# Power_Distribution.net
KiCad netlist of a schematic drawn in EAGLE
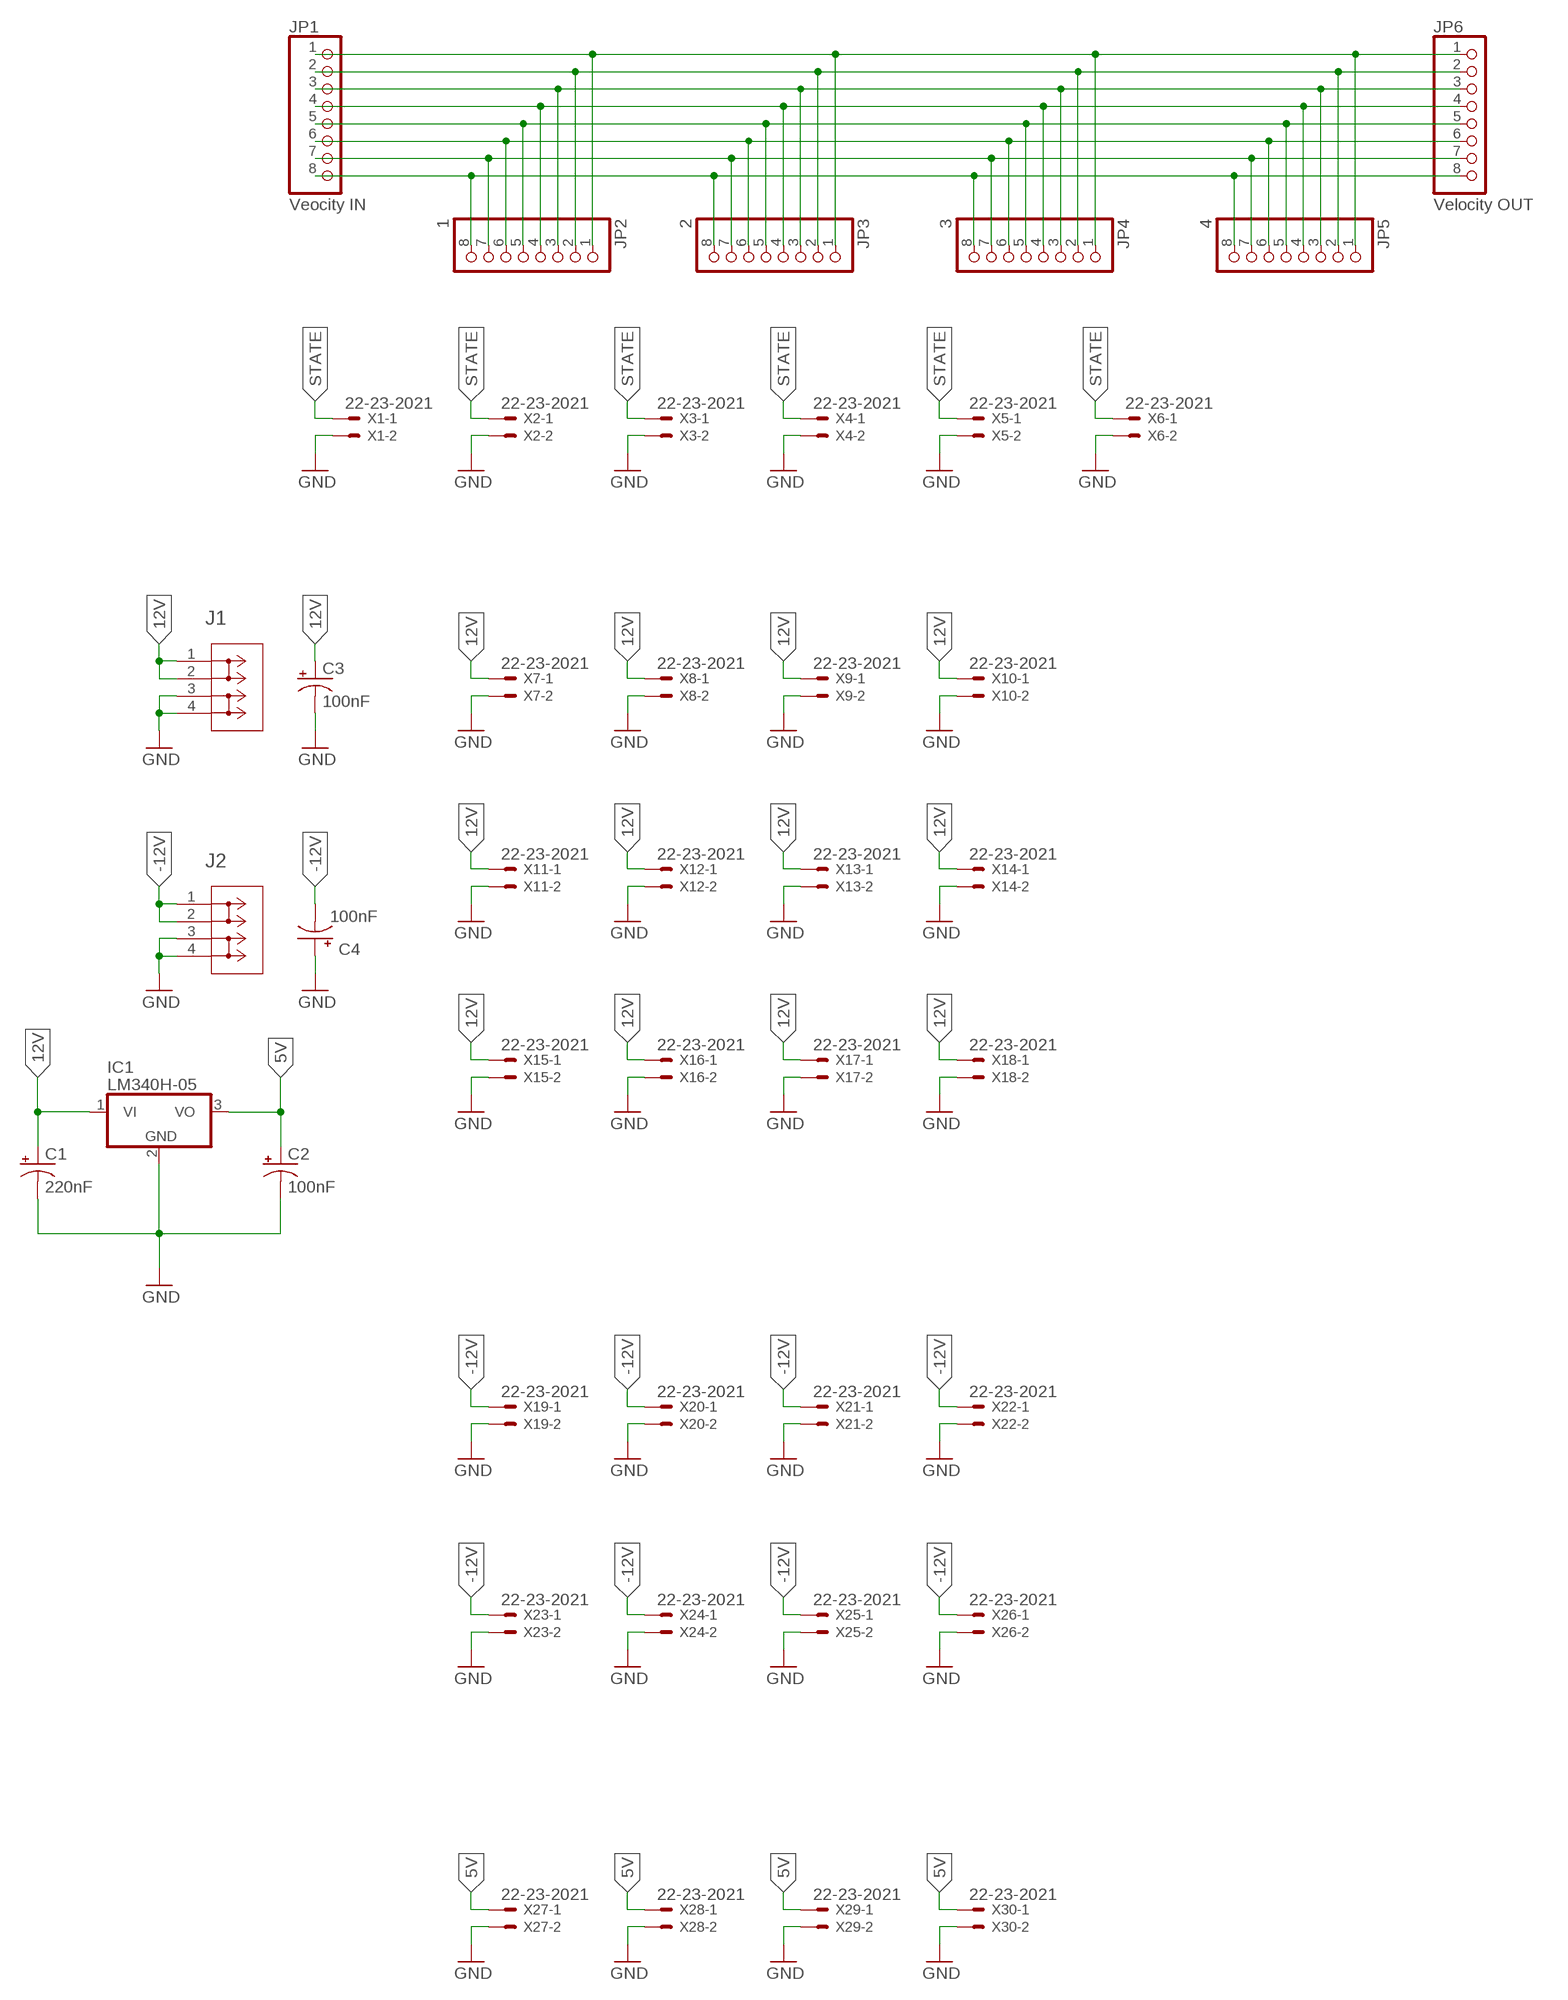
[diagram p0: schematic, sheet 1]

(export (version "E")
  (design (tool "Eeschema 10.0.6"))
  (components
    (comp (ref "C1")
      (value "220nF")
      (footprint "eagle-import:E2-5")
      (libsource (lib "eagle-import") (part "CPOL-USE2-5"))
    )
    (comp (ref "C2")
      (value "100nF")
      (footprint "eagle-import:E1,8-4")
      (libsource (lib "eagle-import") (part "CPOL-USE1.8-4"))
    )
    (comp (ref "C3")
      (value "100nF")
      (footprint "eagle-import:E1,8-4")
      (libsource (lib "eagle-import") (part "CPOL-USE1.8-4"))
    )
    (comp (ref "C4")
      (value "100nF")
      (footprint "eagle-import:E1,8-4")
      (libsource (lib "eagle-import") (part "CPOL-USE1.8-4"))
    )
    (comp (ref "IC1")
      (value "LM340H-05")
      (footprint "eagle-import:TO220H")
      (libsource (lib "eagle-import") (part "LM340?-H05"))
    )
    (comp (ref "J1")
      (value "691256610002")
      (footprint "eagle-import:CONN_691256610002_WRE")
      (fields (field (name "COPYRIGHT") "Copyright (C) 2024 Ultra Librarian. All rights reserved."))
      (libsource (lib "eagle-import") (part "691256610002"))
    )
    (comp (ref "J2")
      (value "691256610002")
      (footprint "eagle-import:CONN_691256610002_WRE")
      (fields (field (name "COPYRIGHT") "Copyright (C) 2024 Ultra Librarian. All rights reserved."))
      (libsource (lib "eagle-import") (part "691256610002"))
    )
    (comp (ref "JP1")
      (value "Veocity IN")
      (footprint "eagle-import:1X08-BIG")
      (libsource (lib "eagle-import") (part "PINHD-1X8BIG"))
    )
    (comp (ref "JP2")
      (value "1")
      (footprint "eagle-import:1X08-BIG")
      (libsource (lib "eagle-import") (part "PINHD-1X8BIG"))
    )
    (comp (ref "JP3")
      (value "2")
      (footprint "eagle-import:1X08-BIG")
      (libsource (lib "eagle-import") (part "PINHD-1X8BIG"))
    )
    (comp (ref "JP4")
      (value "3")
      (footprint "eagle-import:1X08-BIG")
      (libsource (lib "eagle-import") (part "PINHD-1X8BIG"))
    )
    (comp (ref "JP5")
      (value "4")
      (footprint "eagle-import:1X08-BIG")
      (libsource (lib "eagle-import") (part "PINHD-1X8BIG"))
    )
    (comp (ref "JP6")
      (value "Velocity OUT")
      (footprint "eagle-import:1X08-BIG")
      (libsource (lib "eagle-import") (part "PINHD-1X8BIG"))
    )
    (comp (ref "X1")
      (value "22-23-2021")
      (footprint "eagle-import:22-23-2021")
      (fields (field (name "MF") "MOLEX"))
      (libsource (lib "eagle-import") (part "22-23-2021"))
    )
    (comp (ref "X2")
      (value "22-23-2021")
      (footprint "eagle-import:22-23-2021")
      (fields (field (name "MF") "MOLEX"))
      (libsource (lib "eagle-import") (part "22-23-2021"))
    )
    (comp (ref "X3")
      (value "22-23-2021")
      (footprint "eagle-import:22-23-2021")
      (fields (field (name "MF") "MOLEX"))
      (libsource (lib "eagle-import") (part "22-23-2021"))
    )
    (comp (ref "X4")
      (value "22-23-2021")
      (footprint "eagle-import:22-23-2021")
      (fields (field (name "MF") "MOLEX"))
      (libsource (lib "eagle-import") (part "22-23-2021"))
    )
    (comp (ref "X5")
      (value "22-23-2021")
      (footprint "eagle-import:22-23-2021")
      (fields (field (name "MF") "MOLEX"))
      (libsource (lib "eagle-import") (part "22-23-2021"))
    )
    (comp (ref "X6")
      (value "22-23-2021")
      (footprint "eagle-import:22-23-2021")
      (fields (field (name "MF") "MOLEX"))
      (libsource (lib "eagle-import") (part "22-23-2021"))
    )
    (comp (ref "X7")
      (value "22-23-2021")
      (footprint "eagle-import:22-23-2021")
      (fields (field (name "MF") "MOLEX"))
      (libsource (lib "eagle-import") (part "22-23-2021"))
    )
    (comp (ref "X8")
      (value "22-23-2021")
      (footprint "eagle-import:22-23-2021")
      (fields (field (name "MF") "MOLEX"))
      (libsource (lib "eagle-import") (part "22-23-2021"))
    )
    (comp (ref "X9")
      (value "22-23-2021")
      (footprint "eagle-import:22-23-2021")
      (fields (field (name "MF") "MOLEX"))
      (libsource (lib "eagle-import") (part "22-23-2021"))
    )
    (comp (ref "X10")
      (value "22-23-2021")
      (footprint "eagle-import:22-23-2021")
      (fields (field (name "MF") "MOLEX"))
      (libsource (lib "eagle-import") (part "22-23-2021"))
    )
    (comp (ref "X11")
      (value "22-23-2021")
      (footprint "eagle-import:22-23-2021")
      (fields (field (name "MF") "MOLEX"))
      (libsource (lib "eagle-import") (part "22-23-2021"))
    )
    (comp (ref "X12")
      (value "22-23-2021")
      (footprint "eagle-import:22-23-2021")
      (fields (field (name "MF") "MOLEX"))
      (libsource (lib "eagle-import") (part "22-23-2021"))
    )
    (comp (ref "X13")
      (value "22-23-2021")
      (footprint "eagle-import:22-23-2021")
      (fields (field (name "MF") "MOLEX"))
      (libsource (lib "eagle-import") (part "22-23-2021"))
    )
    (comp (ref "X14")
      (value "22-23-2021")
      (footprint "eagle-import:22-23-2021")
      (fields (field (name "MF") "MOLEX"))
      (libsource (lib "eagle-import") (part "22-23-2021"))
    )
    (comp (ref "X15")
      (value "22-23-2021")
      (footprint "eagle-import:22-23-2021")
      (fields (field (name "MF") "MOLEX"))
      (libsource (lib "eagle-import") (part "22-23-2021"))
    )
    (comp (ref "X16")
      (value "22-23-2021")
      (footprint "eagle-import:22-23-2021")
      (fields (field (name "MF") "MOLEX"))
      (libsource (lib "eagle-import") (part "22-23-2021"))
    )
    (comp (ref "X17")
      (value "22-23-2021")
      (footprint "eagle-import:22-23-2021")
      (fields (field (name "MF") "MOLEX"))
      (libsource (lib "eagle-import") (part "22-23-2021"))
    )
    (comp (ref "X18")
      (value "22-23-2021")
      (footprint "eagle-import:22-23-2021")
      (fields (field (name "MF") "MOLEX"))
      (libsource (lib "eagle-import") (part "22-23-2021"))
    )
    (comp (ref "X19")
      (value "22-23-2021")
      (footprint "eagle-import:22-23-2021")
      (fields (field (name "MF") "MOLEX"))
      (libsource (lib "eagle-import") (part "22-23-2021"))
    )
    (comp (ref "X20")
      (value "22-23-2021")
      (footprint "eagle-import:22-23-2021")
      (fields (field (name "MF") "MOLEX"))
      (libsource (lib "eagle-import") (part "22-23-2021"))
    )
    (comp (ref "X21")
      (value "22-23-2021")
      (footprint "eagle-import:22-23-2021")
      (fields (field (name "MF") "MOLEX"))
      (libsource (lib "eagle-import") (part "22-23-2021"))
    )
    (comp (ref "X22")
      (value "22-23-2021")
      (footprint "eagle-import:22-23-2021")
      (fields (field (name "MF") "MOLEX"))
      (libsource (lib "eagle-import") (part "22-23-2021"))
    )
    (comp (ref "X23")
      (value "22-23-2021")
      (footprint "eagle-import:22-23-2021")
      (fields (field (name "MF") "MOLEX"))
      (libsource (lib "eagle-import") (part "22-23-2021"))
    )
    (comp (ref "X24")
      (value "22-23-2021")
      (footprint "eagle-import:22-23-2021")
      (fields (field (name "MF") "MOLEX"))
      (libsource (lib "eagle-import") (part "22-23-2021"))
    )
    (comp (ref "X25")
      (value "22-23-2021")
      (footprint "eagle-import:22-23-2021")
      (fields (field (name "MF") "MOLEX"))
      (libsource (lib "eagle-import") (part "22-23-2021"))
    )
    (comp (ref "X26")
      (value "22-23-2021")
      (footprint "eagle-import:22-23-2021")
      (fields (field (name "MF") "MOLEX"))
      (libsource (lib "eagle-import") (part "22-23-2021"))
    )
    (comp (ref "X27")
      (value "22-23-2021")
      (footprint "eagle-import:22-23-2021")
      (fields (field (name "MF") "MOLEX"))
      (libsource (lib "eagle-import") (part "22-23-2021"))
    )
    (comp (ref "X28")
      (value "22-23-2021")
      (footprint "eagle-import:22-23-2021")
      (fields (field (name "MF") "MOLEX"))
      (libsource (lib "eagle-import") (part "22-23-2021"))
    )
    (comp (ref "X29")
      (value "22-23-2021")
      (footprint "eagle-import:22-23-2021")
      (fields (field (name "MF") "MOLEX"))
      (libsource (lib "eagle-import") (part "22-23-2021"))
    )
    (comp (ref "X30")
      (value "22-23-2021")
      (footprint "eagle-import:22-23-2021")
      (fields (field (name "MF") "MOLEX"))
      (libsource (lib "eagle-import") (part "22-23-2021"))
    )
  )
  (nets
    (net (code "1") (name "-12V") (class "Default")
      (node (ref "C4") (pin "-") (pinfunction "-_-") (pintype "passive"))
      (node (ref "J2") (pin "1") (pinfunction "1_1") (pintype "passive"))
      (node (ref "J2") (pin "2") (pinfunction "2_2") (pintype "passive"))
      (node (ref "X19") (pin "1") (pinfunction "S_1") (pintype "passive"))
      (node (ref "X20") (pin "1") (pinfunction "S_1") (pintype "passive"))
      (node (ref "X21") (pin "1") (pinfunction "S_1") (pintype "passive"))
      (node (ref "X22") (pin "1") (pinfunction "S_1") (pintype "passive"))
      (node (ref "X23") (pin "1") (pinfunction "S_1") (pintype "passive"))
      (node (ref "X24") (pin "1") (pinfunction "S_1") (pintype "passive"))
      (node (ref "X25") (pin "1") (pinfunction "S_1") (pintype "passive"))
      (node (ref "X26") (pin "1") (pinfunction "S_1") (pintype "passive"))
    )
    (net (code "2") (name "5V") (class "Default")
      (node (ref "C2") (pin "+") (pinfunction "+_+") (pintype "passive"))
      (node (ref "IC1") (pin "3") (pinfunction "VO_3") (pintype "passive"))
      (node (ref "X27") (pin "1") (pinfunction "S_1") (pintype "passive"))
      (node (ref "X28") (pin "1") (pinfunction "S_1") (pintype "passive"))
      (node (ref "X29") (pin "1") (pinfunction "S_1") (pintype "passive"))
      (node (ref "X30") (pin "1") (pinfunction "S_1") (pintype "passive"))
    )
    (net (code "3") (name "12V") (class "Default")
      (node (ref "C1") (pin "+") (pinfunction "+_+") (pintype "passive"))
      (node (ref "C3") (pin "+") (pinfunction "+_+") (pintype "passive"))
      (node (ref "IC1") (pin "1") (pinfunction "VI_1") (pintype "input"))
      (node (ref "J1") (pin "1") (pinfunction "1_1") (pintype "passive"))
      (node (ref "J1") (pin "2") (pinfunction "2_2") (pintype "passive"))
      (node (ref "X10") (pin "1") (pinfunction "S_1") (pintype "passive"))
      (node (ref "X11") (pin "1") (pinfunction "S_1") (pintype "passive"))
      (node (ref "X12") (pin "1") (pinfunction "S_1") (pintype "passive"))
      (node (ref "X13") (pin "1") (pinfunction "S_1") (pintype "passive"))
      (node (ref "X14") (pin "1") (pinfunction "S_1") (pintype "passive"))
      (node (ref "X15") (pin "1") (pinfunction "S_1") (pintype "passive"))
      (node (ref "X16") (pin "1") (pinfunction "S_1") (pintype "passive"))
      (node (ref "X17") (pin "1") (pinfunction "S_1") (pintype "passive"))
      (node (ref "X18") (pin "1") (pinfunction "S_1") (pintype "passive"))
      (node (ref "X7") (pin "1") (pinfunction "S_1") (pintype "passive"))
      (node (ref "X8") (pin "1") (pinfunction "S_1") (pintype "passive"))
      (node (ref "X9") (pin "1") (pinfunction "S_1") (pintype "passive"))
    )
    (net (code "4") (name "GND") (class "Default")
      (node (ref "C1") (pin "-") (pinfunction "-_-") (pintype "passive"))
      (node (ref "C2") (pin "-") (pinfunction "-_-") (pintype "passive"))
      (node (ref "C3") (pin "-") (pinfunction "-_-") (pintype "passive"))
      (node (ref "C4") (pin "+") (pinfunction "+_+") (pintype "passive"))
      (node (ref "IC1") (pin "2") (pinfunction "GND_2") (pintype "passive"))
      (node (ref "J1") (pin "3") (pinfunction "3_3") (pintype "passive"))
      (node (ref "J1") (pin "4") (pinfunction "4_4") (pintype "passive"))
      (node (ref "J2") (pin "3") (pinfunction "3_3") (pintype "passive"))
      (node (ref "J2") (pin "4") (pinfunction "4_4") (pintype "passive"))
      (node (ref "X1") (pin "2") (pinfunction "S_2") (pintype "passive"))
      (node (ref "X10") (pin "2") (pinfunction "S_2") (pintype "passive"))
      (node (ref "X11") (pin "2") (pinfunction "S_2") (pintype "passive"))
      (node (ref "X12") (pin "2") (pinfunction "S_2") (pintype "passive"))
      (node (ref "X13") (pin "2") (pinfunction "S_2") (pintype "passive"))
      (node (ref "X14") (pin "2") (pinfunction "S_2") (pintype "passive"))
      (node (ref "X15") (pin "2") (pinfunction "S_2") (pintype "passive"))
      (node (ref "X16") (pin "2") (pinfunction "S_2") (pintype "passive"))
      (node (ref "X17") (pin "2") (pinfunction "S_2") (pintype "passive"))
      (node (ref "X18") (pin "2") (pinfunction "S_2") (pintype "passive"))
      (node (ref "X19") (pin "2") (pinfunction "S_2") (pintype "passive"))
      (node (ref "X2") (pin "2") (pinfunction "S_2") (pintype "passive"))
      (node (ref "X20") (pin "2") (pinfunction "S_2") (pintype "passive"))
      (node (ref "X21") (pin "2") (pinfunction "S_2") (pintype "passive"))
      (node (ref "X22") (pin "2") (pinfunction "S_2") (pintype "passive"))
      (node (ref "X23") (pin "2") (pinfunction "S_2") (pintype "passive"))
      (node (ref "X24") (pin "2") (pinfunction "S_2") (pintype "passive"))
      (node (ref "X25") (pin "2") (pinfunction "S_2") (pintype "passive"))
      (node (ref "X26") (pin "2") (pinfunction "S_2") (pintype "passive"))
      (node (ref "X27") (pin "2") (pinfunction "S_2") (pintype "passive"))
      (node (ref "X28") (pin "2") (pinfunction "S_2") (pintype "passive"))
      (node (ref "X29") (pin "2") (pinfunction "S_2") (pintype "passive"))
      (node (ref "X3") (pin "2") (pinfunction "S_2") (pintype "passive"))
      (node (ref "X30") (pin "2") (pinfunction "S_2") (pintype "passive"))
      (node (ref "X4") (pin "2") (pinfunction "S_2") (pintype "passive"))
      (node (ref "X5") (pin "2") (pinfunction "S_2") (pintype "passive"))
      (node (ref "X6") (pin "2") (pinfunction "S_2") (pintype "passive"))
      (node (ref "X7") (pin "2") (pinfunction "S_2") (pintype "passive"))
      (node (ref "X8") (pin "2") (pinfunction "S_2") (pintype "passive"))
      (node (ref "X9") (pin "2") (pinfunction "S_2") (pintype "passive"))
    )
    (net (code "5") (name "Net-(JP1-Pad1)") (class "Default")
      (node (ref "JP1") (pin "1") (pinfunction "1_1") (pintype "passive"))
      (node (ref "JP2") (pin "1") (pinfunction "1_1") (pintype "passive"))
      (node (ref "JP3") (pin "1") (pinfunction "1_1") (pintype "passive"))
      (node (ref "JP4") (pin "1") (pinfunction "1_1") (pintype "passive"))
      (node (ref "JP5") (pin "1") (pinfunction "1_1") (pintype "passive"))
      (node (ref "JP6") (pin "1") (pinfunction "1_1") (pintype "passive"))
    )
    (net (code "6") (name "Net-(JP1-Pad2)") (class "Default")
      (node (ref "JP1") (pin "2") (pinfunction "2_2") (pintype "passive"))
      (node (ref "JP2") (pin "2") (pinfunction "2_2") (pintype "passive"))
      (node (ref "JP3") (pin "2") (pinfunction "2_2") (pintype "passive"))
      (node (ref "JP4") (pin "2") (pinfunction "2_2") (pintype "passive"))
      (node (ref "JP5") (pin "2") (pinfunction "2_2") (pintype "passive"))
      (node (ref "JP6") (pin "2") (pinfunction "2_2") (pintype "passive"))
    )
    (net (code "7") (name "Net-(JP1-Pad3)") (class "Default")
      (node (ref "JP1") (pin "3") (pinfunction "3_3") (pintype "passive"))
      (node (ref "JP2") (pin "3") (pinfunction "3_3") (pintype "passive"))
      (node (ref "JP3") (pin "3") (pinfunction "3_3") (pintype "passive"))
      (node (ref "JP4") (pin "3") (pinfunction "3_3") (pintype "passive"))
      (node (ref "JP5") (pin "3") (pinfunction "3_3") (pintype "passive"))
      (node (ref "JP6") (pin "3") (pinfunction "3_3") (pintype "passive"))
    )
    (net (code "8") (name "Net-(JP1-Pad4)") (class "Default")
      (node (ref "JP1") (pin "4") (pinfunction "4_4") (pintype "passive"))
      (node (ref "JP2") (pin "4") (pinfunction "4_4") (pintype "passive"))
      (node (ref "JP3") (pin "4") (pinfunction "4_4") (pintype "passive"))
      (node (ref "JP4") (pin "4") (pinfunction "4_4") (pintype "passive"))
      (node (ref "JP5") (pin "4") (pinfunction "4_4") (pintype "passive"))
      (node (ref "JP6") (pin "4") (pinfunction "4_4") (pintype "passive"))
    )
    (net (code "9") (name "Net-(JP1-Pad5)") (class "Default")
      (node (ref "JP1") (pin "5") (pinfunction "5_5") (pintype "passive"))
      (node (ref "JP2") (pin "5") (pinfunction "5_5") (pintype "passive"))
      (node (ref "JP3") (pin "5") (pinfunction "5_5") (pintype "passive"))
      (node (ref "JP4") (pin "5") (pinfunction "5_5") (pintype "passive"))
      (node (ref "JP5") (pin "5") (pinfunction "5_5") (pintype "passive"))
      (node (ref "JP6") (pin "5") (pinfunction "5_5") (pintype "passive"))
    )
    (net (code "10") (name "Net-(JP1-Pad6)") (class "Default")
      (node (ref "JP1") (pin "6") (pinfunction "6_6") (pintype "passive"))
      (node (ref "JP2") (pin "6") (pinfunction "6_6") (pintype "passive"))
      (node (ref "JP3") (pin "6") (pinfunction "6_6") (pintype "passive"))
      (node (ref "JP4") (pin "6") (pinfunction "6_6") (pintype "passive"))
      (node (ref "JP5") (pin "6") (pinfunction "6_6") (pintype "passive"))
      (node (ref "JP6") (pin "6") (pinfunction "6_6") (pintype "passive"))
    )
    (net (code "11") (name "Net-(JP1-Pad7)") (class "Default")
      (node (ref "JP1") (pin "7") (pinfunction "7_7") (pintype "passive"))
      (node (ref "JP2") (pin "7") (pinfunction "7_7") (pintype "passive"))
      (node (ref "JP3") (pin "7") (pinfunction "7_7") (pintype "passive"))
      (node (ref "JP4") (pin "7") (pinfunction "7_7") (pintype "passive"))
      (node (ref "JP5") (pin "7") (pinfunction "7_7") (pintype "passive"))
      (node (ref "JP6") (pin "7") (pinfunction "7_7") (pintype "passive"))
    )
    (net (code "12") (name "Net-(JP1-Pad8)") (class "Default")
      (node (ref "JP1") (pin "8") (pinfunction "8_8") (pintype "passive"))
      (node (ref "JP2") (pin "8") (pinfunction "8_8") (pintype "passive"))
      (node (ref "JP3") (pin "8") (pinfunction "8_8") (pintype "passive"))
      (node (ref "JP4") (pin "8") (pinfunction "8_8") (pintype "passive"))
      (node (ref "JP5") (pin "8") (pinfunction "8_8") (pintype "passive"))
      (node (ref "JP6") (pin "8") (pinfunction "8_8") (pintype "passive"))
    )
    (net (code "13") (name "STATE") (class "Default")
      (node (ref "X1") (pin "1") (pinfunction "S_1") (pintype "passive"))
      (node (ref "X2") (pin "1") (pinfunction "S_1") (pintype "passive"))
      (node (ref "X3") (pin "1") (pinfunction "S_1") (pintype "passive"))
      (node (ref "X4") (pin "1") (pinfunction "S_1") (pintype "passive"))
      (node (ref "X5") (pin "1") (pinfunction "S_1") (pintype "passive"))
      (node (ref "X6") (pin "1") (pinfunction "S_1") (pintype "passive"))
    )
  )
)
